# AQM_with_esp32.net
KiCad netlist of a schematic drawn in Altium Designer
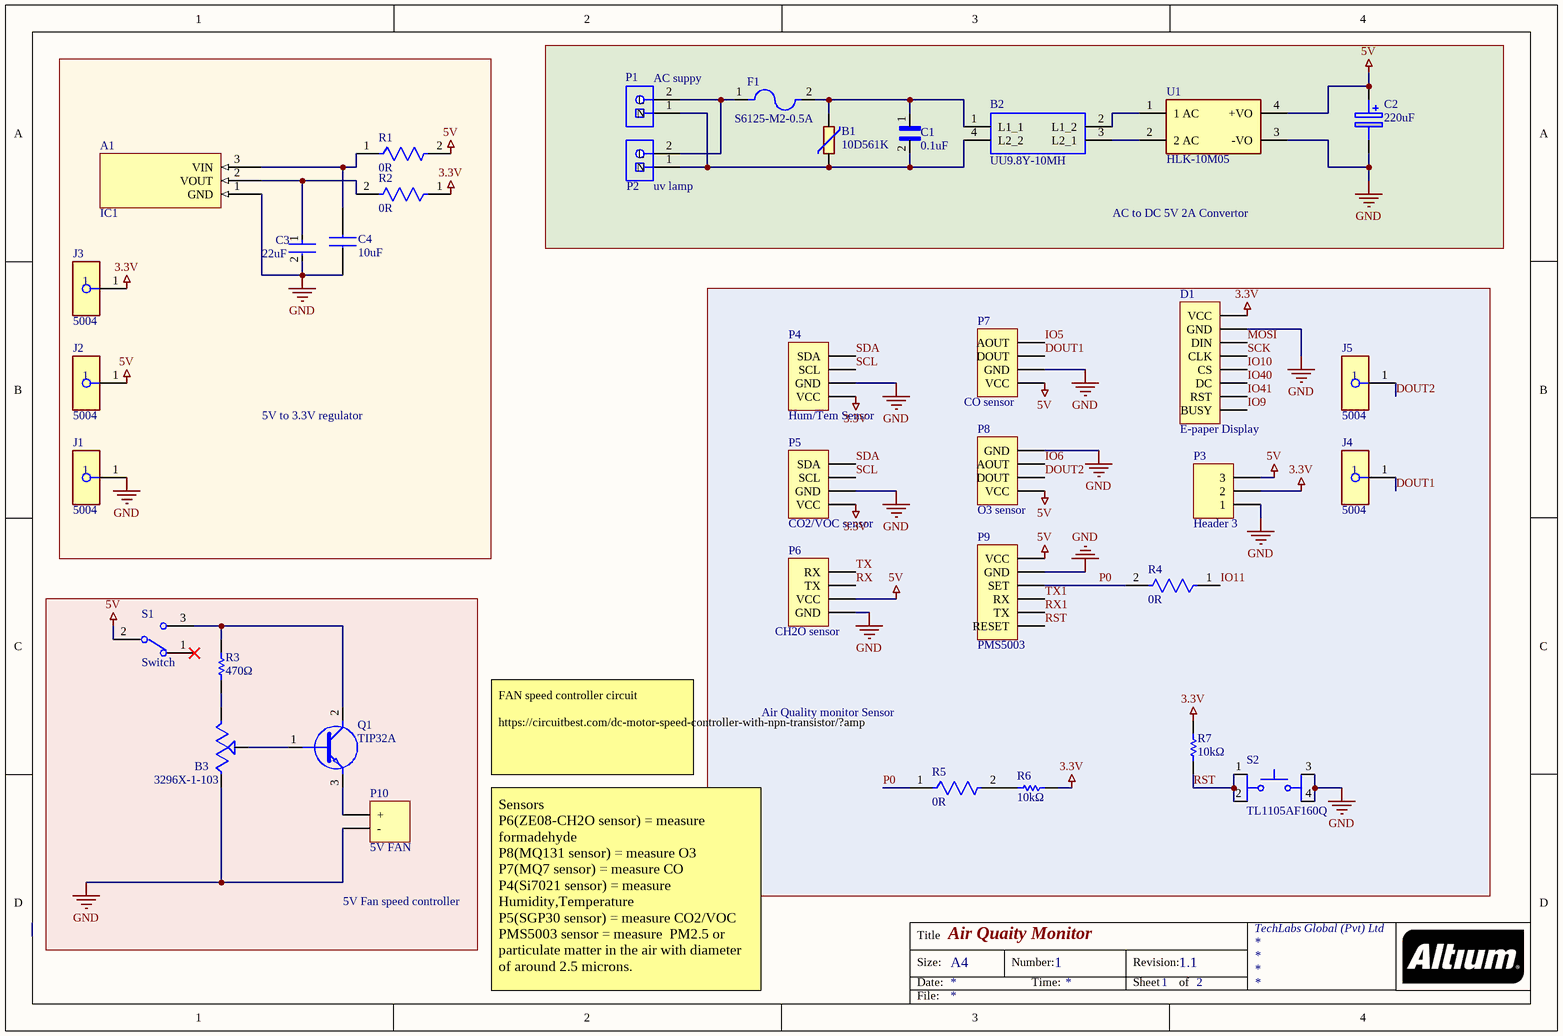
[diagram p0: AQM with esp32.SchDoc]

(export (version "E")
  (design (tool "Eeschema 10.0.6"))
  (components
    (comp (ref "A1")
      (value "IC1")
      (footprint "SOT89-150P350X150-3N")
      (fields
        (field (name "MANUFACTURER") "YONGYUTAI")
        (field (name "MFR. PART #") "AMS1117-3.3")
        (field (name "LCSC PART #") "C2904742")
      )
      (libsource (lib "AMS1117-3.3") (part "IC?"))
    )
    (comp (ref "B1")
      (value "10D561K")
      (footprint "10D561K")
      (description "920V 42.3J 180pF@1kHz 460V 350V 504V~616V 2.5kA Plugin Varistors ROHS")
      (fields (field (name "LCSC PART #") "C113236") (field (name "MANUFACTURER") "Hongzhi Elec"))
      (libsource (lib "10D561K") (part "10D561K"))
    )
    (comp (ref "B2")
      (value "UU9.8Y-10MH")
      (footprint "UU98Y10MH")
      (description "10mH@1kHz 1.2Ω 2 500mA 50V Plugin Common Mode Filters ROHS")
      (fields
        (field (name "MANUFACTURER") "FH (Guangdong Fenghua Advanced Tech)")
        (field (name "LCSC PART #") "C75192")
      )
      (libsource (lib "UU9.8Y-10MH") (part "UU9.8Y-10MH"))
    )
    (comp (ref "B3")
      (value "3296X-1-103")
      (footprint "3296X1223LF")
      (description "±10% 10kΩ Plugin Variable Resistors/Potentiometers ROHS")
      (fields
        (field (name "LCSC PART #") "C118955")
        (field (name "MANUFACTURER") "BOCHEN(Chengdu Guosheng Tech)")
      )
      (libsource (lib "3296X-1-103") (part "3296X-1-103"))
    )
    (comp (ref "C1")
      (value "0.1uF")
      (footprint "MPX-104K275VAC-C-D2")
      (description "X2 100nF ±10% 275V Plugin,P=15mm Suppression Capacitors ROHS")
      (fields (field (name "LCSC PART #") "C914484") (field (name "MANUFACTURER") "NDF"))
      (libsource (lib "X2-104K-275VAC") (part "MPX-104K275VAC-C-D2"))
    )
    (comp (ref "C2")
      (value "220uF")
      (footprint "CAPAE830X1050N")
      (fields
        (field (name "MANUFACTURER") "Nichicon")
        (field (name "MFR. PART #") "UUR1C221MNL1GS")
        (field (name "LCSC PART #") "C445237")
      )
      (libsource (lib "UUR1C221MNL1GS") (part "UUR1C221MNL1GS"))
    )
    (comp (ref "C3")
      (value "22uF")
      (footprint "FP-GRM219-0_2-0_15-IPC_A")
      (description "Chip Multilayer Ceramic Capacitors for General Purpose, 0805, 22uF, X5R, 15%, 20%, 16V")
      (fields (field (name "MFR. PART #") "GRM219R61C226ME15L") (field (name "LCSC PART #") "C162295"))
      (libsource (lib "Altium Content Vault") (part "b4654b650e69147ec39a6b967a45e02"))
    )
    (comp (ref "C4")
      (value "10uF")
      (footprint "CL05A106MQ5NUNC")
      (description "6.3V 10uF X5R ±20% 0402 Multilayer Ceramic Capacitors MLCC - SMD/SMT ROHS")
      (fields
        (field (name "MANUFACTURER") "Samsung Electro-Mechanics")
        (field (name "MFR. PART #") "CL05A106MQ5NUNC")
      )
      (libsource (lib "CL05A106MQ5NUNC") (part "CL05A106MQ5NUNC"))
    )
    (comp (ref "D1")
      (value "E-paper Display")
      (footprint "HDR1X8")
      (description "Header, 8-Pin")
      (fields (field (name "PUBLISHER") "Altium Limited"))
      (libsource (lib "Miscellaneous Connectors") (part "Header 8"))
    )
    (comp (ref "F1")
      (value "S6125-M2-0.5A")
      (footprint "CAPC6125X25N")
      (description "SMD Fuses ROHS")
      (fields (field (name "LCSC PART #") "C845172") (field (name "MANUFACTURER") "SART(Nanjing Sart Tech)"))
      (libsource (lib "S6125-M2-0.5A") (part "S6125-M2-0.5A"))
    )
    (comp (ref "J1")
      (value "5004")
      (footprint "FP-5004-MFG")
      (description "PC TEST POINT MINIATURE YELLOW")
      (fields (field (name "MANUFACTURER") "Keystone") (field (name "LCSC PART #") "C2906762"))
      (libsource (lib "Altium Content Vault") (part "98815daf2f2c152b0c43f5ab9800df6"))
    )
    (comp (ref "J2")
      (value "5004")
      (footprint "FP-5004-MFG")
      (description "PC TEST POINT MINIATURE YELLOW")
      (fields (field (name "MANUFACTURER") "Keystone") (field (name "LCSC PART #") "C2906762"))
      (libsource (lib "Altium Content Vault") (part "98815daf2f2c152b0c43f5ab9800df6"))
    )
    (comp (ref "J3")
      (value "5004")
      (footprint "FP-5004-MFG")
      (description "PC TEST POINT MINIATURE YELLOW")
      (fields (field (name "MANUFACTURER") "Keystone") (field (name "LCSC PART #") "C2906762"))
      (libsource (lib "Altium Content Vault") (part "98815daf2f2c152b0c43f5ab9800df6"))
    )
    (comp (ref "J4")
      (value "5004")
      (footprint "FP-5004-MFG")
      (description "PC TEST POINT MINIATURE YELLOW")
      (fields (field (name "MANUFACTURER") "Keystone") (field (name "LCSC PART #") "C2906762"))
      (libsource (lib "Altium Content Vault") (part "98815daf2f2c152b0c43f5ab9800df6"))
    )
    (comp (ref "J5")
      (value "5004")
      (footprint "FP-5004-MFG")
      (description "PC TEST POINT MINIATURE YELLOW")
      (fields (field (name "MANUFACTURER") "Keystone") (field (name "LCSC PART #") "C2906762"))
      (libsource (lib "Altium Content Vault") (part "98815daf2f2c152b0c43f5ab9800df6"))
    )
    (comp (ref "P1")
      (value "AC suppy")
      (footprint "PHOE-1729128-2_V")
      (description "13.5A 400V Green Straight pin 5.08mm 1 2 Plugin,P=5.08mm Screw terminal ROHS")
      (fields (field (name "MFR. PART #") "1729128") (field (name "LCSC PART #") "C91153"))
      (libsource (lib "Altium Content Vault") (part "CN-2P-F-R2"))
    )
    (comp (ref "P2")
      (value "uv lamp")
      (footprint "PHOE-1729128-2_V")
      (description "13.5A 400V Green Straight pin 5.08mm 1 2 Plugin,P=5.08mm Screw terminal ROHS")
      (fields (field (name "MFR. PART #") "1729128") (field (name "LCSC PART #") "C91153"))
      (libsource (lib "Altium Content Vault") (part "CN-2P-F-R2"))
    )
    (comp (ref "P3")
      (value "Header 3")
      (footprint "HDR1X3")
      (description "Header, 3-Pin")
      (fields (field (name "PUBLISHER") "Altium Limited"))
      (libsource (lib "Miscellaneous Connectors") (part "Header 3"))
    )
    (comp (ref "P4")
      (value "Hum/Tem Sensor")
      (footprint "HDR1X4")
      (description "Si7021 Header, 4-Pin")
      (libsource (lib "Miscellaneous Connectors") (part "Header 4"))
    )
    (comp (ref "P5")
      (value "CO2/VOC sensor")
      (footprint "HDR1X4")
      (description "SGP30 Header, 4-Pin")
      (fields (field (name "PUBLISHER") "Altium Limited"))
      (libsource (lib "Miscellaneous Connectors") (part "Header 4"))
    )
    (comp (ref "P6")
      (value "CH2O sensor")
      (footprint "HDR1X4")
      (description "- Sensor Modules ROHS")
      (fields
        (field (name "MFR. PART #") "ZE08-CH2O")
        (field (name "MANUFACTURER") "Zhengzhou Winsen Elec Tech")
      )
      (libsource (lib "") (part "Header 4_1"))
    )
    (comp (ref "P7")
      (value "CO sensor")
      (footprint "HDR1X4")
      (description "MQ7 Header, 4-Pin")
      (fields (field (name "PUBLISHER") "Altium Limited"))
      (libsource (lib "") (part "Header 4_2"))
    )
    (comp (ref "P8")
      (value "O3 sensor")
      (footprint "HDR1X4")
      (description "MQ131 Header, 4-Pin")
      (fields (field (name "PUBLISHER") "Altium Limited"))
      (libsource (lib "") (part "Header 4_3"))
    )
    (comp (ref "P9")
      (value "PMS5003")
      (footprint "HDR1X6")
      (description "PMS5003 Sensor Modules ROHS")
      (fields (field (name "LCSC PART #") "C91431") (field (name "MANUFACTURER") "Beijing Plantower"))
      (libsource (lib "Miscellaneous Connectors") (part "Header 6"))
    )
    (comp (ref "P10")
      (value "5V FAN")
      (footprint "HDR1X2")
      (description "Header, 2-Pin")
      (fields (field (name "PUBLISHER") "Altium Limited"))
      (libsource (lib "Miscellaneous Connectors") (part "Header 2"))
    )
    (comp (ref "Q1")
      (value "TIP32A")
      (footprint "TO304P498X1010X2089-3P")
      (description "TO-220 Bipolar Transistors - BJT ROHS")
      (fields (field (name "LCSC PART #") "C5122514") (field (name "MANUFACTURER") "Slkor(SLKORMICRO Elec.)"))
      (libsource (lib "2SD313") (part "2SD313"))
    )
    (comp (ref "R1")
      (value "0R")
      (footprint "FP-RC0402-0_4-IPC_A")
      (description "RES SMD 0 OHM JUMPER 1/16W 0402")
      (fields (field (name "MANUFACTURER") "Yageo") (field (name "LCSC PART #") "C106231"))
      (libsource (lib "Altium Content Vault") (part "1029c3af85768c4190bb7ad29bc67b5"))
    )
    (comp (ref "R2")
      (value "0R")
      (footprint "FP-RC0402-0_4-IPC_A")
      (description "RES SMD 0 OHM JUMPER 1/16W 0402")
      (fields (field (name "MANUFACTURER") "Yageo") (field (name "LCSC PART #") "C106231"))
      (libsource (lib "Altium Content Vault") (part "1029c3af85768c4190bb7ad29bc67b5"))
    )
    (comp (ref "R3")
      (value "470Ω")
      (footprint "RESC1608X55X25LL10T15")
      (fields
        (field (name "LCSC PART #") "C114669")
        (field (name "MFR. PART #") "RC0603FR-07470RL")
        (field (name "MANUFACTURER") "YAGEO")
      )
      (libsource (lib "Altium Content Vault") (part "RES-2"))
    )
    (comp (ref "R4")
      (value "0R")
      (footprint "FP-RC0402-0_4-IPC_A")
      (description "RES SMD 0 OHM JUMPER 1/16W 0402")
      (fields (field (name "MANUFACTURER") "Yageo") (field (name "LCSC PART #") "C106231"))
      (libsource (lib "Altium Content Vault") (part "1029c3af85768c4190bb7ad29bc67b5"))
    )
    (comp (ref "R5")
      (value "0R")
      (footprint "FP-RC0402-0_4-IPC_A")
      (description "RES SMD 0 OHM JUMPER 1/16W 0402")
      (fields (field (name "MANUFACTURER") "Yageo") (field (name "LCSC PART #") "C106231"))
      (libsource (lib "Altium Content Vault") (part "1029c3af85768c4190bb7ad29bc67b5"))
    )
    (comp (ref "R6")
      (value "10kΩ")
      (footprint "RESC1005X40X25LL05T10")
      (fields
        (field (name "MFR. PART #") "RC0402FR-0710KL")
        (field (name "MANUFACTURER") "YAGEO")
        (field (name "LCSC PART #") "C60490")
      )
      (libsource (lib "Altium Content Vault") (part "RES"))
    )
    (comp (ref "R7")
      (value "10kΩ")
      (footprint "RESC1005X40X25LL05T10")
      (fields
        (field (name "MFR. PART #") "RC0402FR-0710KL")
        (field (name "MANUFACTURER") "YAGEO")
        (field (name "LCSC PART #") "C60490")
      )
      (libsource (lib "Altium Content Vault") (part "RES"))
    )
    (comp (ref "S1")
      (value "Switch")
      (footprint "SK3245SL1A")
      (fields
        (field (name "MANUFACTURER") "XKB Connectivity")
        (field (name "MFR. PART #") "SK-3245S-L1-A")
        (field (name "LCSC PART #") "C405951")
      )
      (libsource (lib "SK-3245S-L1-A") (part "SK-3245S-L1-A"))
    )
    (comp (ref "S2")
      (value "TL1105AF160Q")
      (footprint "TL1105AF160Q")
      (description "6mm 1.4mm Round Button 50mA Straight 6mm SPST 12V Plugin,6x6mm Tactile Switches ROHS")
      (fields (field (name "MANUFACTURER") "E-Switch") (field (name "LCSC PART #") "C273465"))
      (libsource (lib "TL1105AF160Q") (part "TL1105AF160Q"))
    )
    (comp (ref "U1")
      (value "HLK-10M05")
      (footprint "FP-HLK-10M05-MFG")
      (description "5V 2A 90VAC~265VAC 1 120V~350V Isolated Regulated 10W AC-DC 80% Plugin Power Modules ROHS")
      (fields (field (name "MANUFACTURER") "HI-LINK") (field (name "LCSC PART #") "C403745"))
      (libsource (lib "Altium Content Vault") (part "a65b17ccb3a75dffb3c3e849074403b"))
    )
  )
  (nets
    (net (code "1") (name "/DOUT1") (class "Default")
      (node (ref "J4") (pin "1") (pinfunction "1_1") (pintype "passive"))
      (node (ref "P7") (pin "3") (pinfunction "DOUT_3") (pintype "passive"))
    )
    (net (code "2") (name "/DOUT2") (class "Default")
      (node (ref "J5") (pin "1") (pinfunction "1_1") (pintype "passive"))
      (node (ref "P8") (pin "2") (pinfunction "DOUT_2") (pintype "passive"))
    )
    (net (code "3") (name "/IO5") (class "Default")
      (node (ref "P7") (pin "4") (pinfunction "AOUT_4") (pintype "passive"))
    )
    (net (code "4") (name "/IO6") (class "Default")
      (node (ref "P8") (pin "3") (pinfunction "AOUT_3") (pintype "passive"))
    )
    (net (code "5") (name "/IO9") (class "Default")
      (node (ref "D1") (pin "1") (pinfunction "BUSY_1") (pintype "passive"))
    )
    (net (code "6") (name "/IO10") (class "Default")
      (node (ref "D1") (pin "4") (pinfunction "CS_4") (pintype "passive"))
    )
    (net (code "7") (name "/IO11") (class "Default")
      (node (ref "R4") (pin "1") (pinfunction "1_1") (pintype "passive"))
    )
    (net (code "8") (name "/IO40") (class "Default")
      (node (ref "D1") (pin "3") (pinfunction "DC_3") (pintype "passive"))
    )
    (net (code "9") (name "/IO41") (class "Default")
      (node (ref "D1") (pin "2") (pinfunction "RST_2") (pintype "passive"))
    )
    (net (code "10") (name "/MOSI") (class "Default")
      (node (ref "D1") (pin "6") (pinfunction "DIN_6") (pintype "passive"))
    )
    (net (code "11") (name "/P0") (class "Default")
      (node (ref "P9") (pin "4") (pinfunction "SET_4") (pintype "passive"))
      (node (ref "R4") (pin "2") (pinfunction "2_2") (pintype "passive"))
      (node (ref "R5") (pin "1") (pinfunction "1_1") (pintype "passive"))
    )
    (net (code "12") (name "/RST") (class "Default")
      (node (ref "P9") (pin "1") (pinfunction "RESET_1") (pintype "passive"))
      (node (ref "R7") (pin "2") (pinfunction "2_2") (pintype "passive"))
      (node (ref "S2") (pin "1") (pinfunction "1_1") (pintype "passive"))
      (node (ref "S2") (pin "2") (pinfunction "2_2") (pintype "passive"))
    )
    (net (code "13") (name "/RX") (class "Default")
      (node (ref "P6") (pin "3") (pinfunction "TX_3") (pintype "passive"))
    )
    (net (code "14") (name "/RX1") (class "Default")
      (node (ref "P9") (pin "2") (pinfunction "TX_2") (pintype "passive"))
    )
    (net (code "15") (name "/SCK") (class "Default")
      (node (ref "D1") (pin "5") (pinfunction "CLK_5") (pintype "passive"))
    )
    (net (code "16") (name "/SCL") (class "Default")
      (node (ref "P4") (pin "3") (pinfunction "SCL_3") (pintype "passive"))
      (node (ref "P5") (pin "3") (pinfunction "SCL_3") (pintype "passive"))
    )
    (net (code "17") (name "/SDA") (class "Default")
      (node (ref "P4") (pin "4") (pinfunction "SDA_4") (pintype "passive"))
      (node (ref "P5") (pin "4") (pinfunction "SDA_4") (pintype "passive"))
    )
    (net (code "18") (name "/TX") (class "Default")
      (node (ref "P6") (pin "4") (pinfunction "RX_4") (pintype "passive"))
    )
    (net (code "19") (name "/TX1") (class "Default")
      (node (ref "P9") (pin "3") (pinfunction "RX_3") (pintype "passive"))
    )
    (net (code "20") (name "3.3V") (class "Default")
      (node (ref "D1") (pin "8") (pinfunction "VCC_8") (pintype "passive"))
      (node (ref "J3") (pin "1") (pinfunction "1_1") (pintype "passive"))
      (node (ref "P3") (pin "2") (pinfunction "2_2") (pintype "passive"))
      (node (ref "P4") (pin "1") (pinfunction "VCC_1") (pintype "passive"))
      (node (ref "P5") (pin "1") (pinfunction "VCC_1") (pintype "passive"))
      (node (ref "R2") (pin "1") (pinfunction "1_1") (pintype "passive"))
      (node (ref "R6") (pin "1") (pinfunction "1_1") (pintype "passive"))
      (node (ref "R7") (pin "1") (pinfunction "1_1") (pintype "passive"))
    )
    (net (code "21") (name "5V") (class "Default")
      (node (ref "C2") (pin "1") (pinfunction "+_1") (pintype "passive"))
      (node (ref "J2") (pin "1") (pinfunction "1_1") (pintype "passive"))
      (node (ref "P3") (pin "3") (pinfunction "3_3") (pintype "passive"))
      (node (ref "P6") (pin "2") (pinfunction "VCC_2") (pintype "passive"))
      (node (ref "P7") (pin "1") (pinfunction "VCC_1") (pintype "passive"))
      (node (ref "P8") (pin "1") (pinfunction "VCC_1") (pintype "passive"))
      (node (ref "P9") (pin "6") (pinfunction "VCC_6") (pintype "passive"))
      (node (ref "R1") (pin "2") (pinfunction "2_2") (pintype "passive"))
      (node (ref "S1") (pin "2") (pinfunction "2_2") (pintype "passive"))
      (node (ref "U1") (pin "4") (pinfunction "+VO_4") (pintype "power_in"))
    )
    (net (code "22") (name "GND") (class "Default")
      (node (ref "A1") (pin "1") (pinfunction "GND_1") (pintype "input"))
      (node (ref "B3") (pin "1") (pinfunction "A_1") (pintype "passive"))
      (node (ref "C2") (pin "2") (pinfunction "-_2") (pintype "passive"))
      (node (ref "C3") (pin "2") (pinfunction "2_2") (pintype "passive"))
      (node (ref "C4") (pin "1") (pinfunction "1_1") (pintype "passive"))
      (node (ref "D1") (pin "7") (pinfunction "GND_7") (pintype "passive"))
      (node (ref "J1") (pin "1") (pinfunction "1_1") (pintype "passive"))
      (node (ref "P10") (pin "2") (pinfunction "-_2") (pintype "passive"))
      (node (ref "P3") (pin "1") (pinfunction "1_1") (pintype "passive"))
      (node (ref "P4") (pin "2") (pinfunction "GND_2") (pintype "passive"))
      (node (ref "P5") (pin "2") (pinfunction "GND_2") (pintype "passive"))
      (node (ref "P6") (pin "1") (pinfunction "GND_1") (pintype "passive"))
      (node (ref "P7") (pin "2") (pinfunction "GND_2") (pintype "passive"))
      (node (ref "P8") (pin "4") (pinfunction "GND_4") (pintype "passive"))
      (node (ref "P9") (pin "5") (pinfunction "GND_5") (pintype "passive"))
      (node (ref "S2") (pin "3") (pinfunction "3_3") (pintype "passive"))
      (node (ref "S2") (pin "4") (pinfunction "4_4") (pintype "passive"))
      (node (ref "U1") (pin "3") (pinfunction "-VO_3") (pintype "power_in"))
    )
    (net (code "23") (name "Net-(A1-VIN)") (class "Default")
      (node (ref "A1") (pin "3") (pinfunction "VIN_3") (pintype "input"))
      (node (ref "C4") (pin "2") (pinfunction "2_2") (pintype "passive"))
      (node (ref "R1") (pin "1") (pinfunction "1_1") (pintype "passive"))
    )
    (net (code "24") (name "Net-(A1-VOUT)") (class "Default")
      (node (ref "A1") (pin "2") (pinfunction "VOUT_2") (pintype "input"))
      (node (ref "C3") (pin "1") (pinfunction "1_1") (pintype "passive"))
      (node (ref "R2") (pin "2") (pinfunction "2_2") (pintype "passive"))
    )
    (net (code "25") (name "Net-(B2-L1_1)") (class "Default")
      (node (ref "B1") (pin "1") (pinfunction "1_1") (pintype "passive"))
      (node (ref "B2") (pin "1") (pinfunction "L1_1_1") (pintype "passive"))
      (node (ref "C1") (pin "1") (pinfunction "1_1") (pintype "passive"))
      (node (ref "F1") (pin "2") (pinfunction "2_2") (pintype "passive"))
    )
    (net (code "26") (name "Net-(B2-L1_2)") (class "Default")
      (node (ref "B2") (pin "2") (pinfunction "L1_2_2") (pintype "passive"))
      (node (ref "U1") (pin "1") (pinfunction "1_AC_1") (pintype "passive"))
    )
    (net (code "27") (name "Net-(B2-L2_1)") (class "Default")
      (node (ref "B2") (pin "3") (pinfunction "L2_1_3") (pintype "passive"))
      (node (ref "U1") (pin "2") (pinfunction "2_AC_2") (pintype "passive"))
    )
    (net (code "28") (name "Net-(B2-L2_2)") (class "Default")
      (node (ref "B1") (pin "2") (pinfunction "2_2") (pintype "passive"))
      (node (ref "B2") (pin "4") (pinfunction "L2_2_4") (pintype "passive"))
      (node (ref "C1") (pin "2") (pinfunction "2_2") (pintype "passive"))
      (node (ref "P1") (pin "1") (pinfunction "N_1") (pintype "passive"))
      (node (ref "P2") (pin "1") (pinfunction "N_1") (pintype "passive"))
    )
    (net (code "29") (name "Net-(B3-B)") (class "Default")
      (node (ref "B3") (pin "2") (pinfunction "B_2") (pintype "passive"))
      (node (ref "Q1") (pin "1") (pinfunction "B_1") (pintype "passive"))
    )
    (net (code "30") (name "Net-(B3-C)") (class "Default")
      (node (ref "B3") (pin "3") (pinfunction "C_3") (pintype "passive"))
      (node (ref "R3") (pin "1") (pinfunction "1_1") (pintype "passive"))
    )
    (net (code "31") (name "Net-(P1-L)") (class "Default")
      (node (ref "F1") (pin "1") (pinfunction "1_1") (pintype "passive"))
      (node (ref "P1") (pin "2") (pinfunction "L_2") (pintype "passive"))
      (node (ref "P2") (pin "2") (pinfunction "L_2") (pintype "passive"))
    )
    (net (code "32") (name "Net-(P10-+)") (class "Default")
      (node (ref "P10") (pin "1") (pinfunction "+_1") (pintype "passive"))
      (node (ref "Q1") (pin "3") (pinfunction "E_3") (pintype "passive"))
    )
    (net (code "33") (name "Net-(Q1-C)") (class "Default")
      (node (ref "Q1") (pin "2") (pinfunction "C_2") (pintype "passive"))
      (node (ref "R3") (pin "2") (pinfunction "2_2") (pintype "passive"))
      (node (ref "S1") (pin "3") (pinfunction "3_3") (pintype "passive"))
    )
    (net (code "34") (name "Net-(R5-Pad2)") (class "Default")
      (node (ref "R5") (pin "2") (pinfunction "2_2") (pintype "passive"))
      (node (ref "R6") (pin "2") (pinfunction "2_2") (pintype "passive"))
    )
    (net (code "35") (name "unconnected-(S1-Pad1)") (class "Default")
      (node (ref "S1") (pin "1") (pinfunction "1_1") (pintype "passive+no_connect"))
    )
  )
)
